# max2880base0.net
KiCad netlist of a schematic drawn in EAGLE
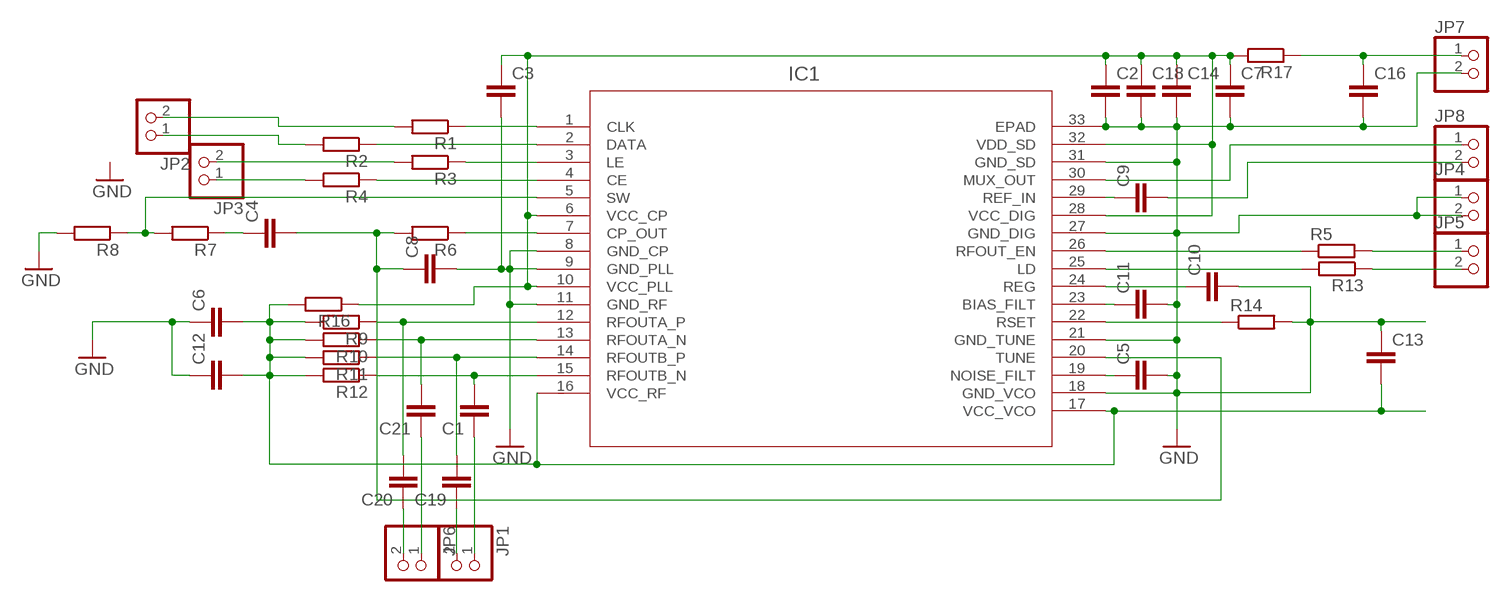
[diagram p0: schematic, sheet 1]

(export (version "E")
  (design (tool "Eeschema 10.0.6"))
  (components
    (comp (ref "C1")
      (value "C-EUC0805")
      (footprint "eagle-import:C0805")
      (libsource (lib "eagle-import") (part "C-EUC0805"))
    )
    (comp (ref "C2")
      (value "C-EUC0805")
      (footprint "eagle-import:C0805")
      (libsource (lib "eagle-import") (part "C-EUC0805"))
    )
    (comp (ref "C3")
      (value "C-EUC0805")
      (footprint "eagle-import:C0805")
      (libsource (lib "eagle-import") (part "C-EUC0805"))
    )
    (comp (ref "C4")
      (value "C-EUC0805")
      (footprint "eagle-import:C0805")
      (libsource (lib "eagle-import") (part "C-EUC0805"))
    )
    (comp (ref "C5")
      (value "C-EUC0805")
      (footprint "eagle-import:C0805")
      (libsource (lib "eagle-import") (part "C-EUC0805"))
    )
    (comp (ref "C6")
      (value "C-EUC0805")
      (footprint "eagle-import:C0805")
      (libsource (lib "eagle-import") (part "C-EUC0805"))
    )
    (comp (ref "C7")
      (value "C-EUC0805")
      (footprint "eagle-import:C0805")
      (libsource (lib "eagle-import") (part "C-EUC0805"))
    )
    (comp (ref "C8")
      (value "C-EUC0805")
      (footprint "eagle-import:C0805")
      (libsource (lib "eagle-import") (part "C-EUC0805"))
    )
    (comp (ref "C9")
      (value "C-EUC0805")
      (footprint "eagle-import:C0805")
      (libsource (lib "eagle-import") (part "C-EUC0805"))
    )
    (comp (ref "C10")
      (value "C-EUC0805")
      (footprint "eagle-import:C0805")
      (libsource (lib "eagle-import") (part "C-EUC0805"))
    )
    (comp (ref "C11")
      (value "C-EUC0805")
      (footprint "eagle-import:C0805")
      (libsource (lib "eagle-import") (part "C-EUC0805"))
    )
    (comp (ref "C12")
      (value "C-EUC0805")
      (footprint "eagle-import:C0805")
      (libsource (lib "eagle-import") (part "C-EUC0805"))
    )
    (comp (ref "C13")
      (value "C-EUC1206")
      (footprint "eagle-import:C1206")
      (libsource (lib "eagle-import") (part "C-EUC1206"))
    )
    (comp (ref "C14")
      (value "C-EUC1206")
      (footprint "eagle-import:C1206")
      (libsource (lib "eagle-import") (part "C-EUC1206"))
    )
    (comp (ref "C16")
      (value "C-EUC1206")
      (footprint "eagle-import:C1206")
      (libsource (lib "eagle-import") (part "C-EUC1206"))
    )
    (comp (ref "C18")
      (value "C-EUC1808")
      (footprint "eagle-import:C1808")
      (libsource (lib "eagle-import") (part "C-EUC1808"))
    )
    (comp (ref "C19")
      (value "C-EUC0805")
      (footprint "eagle-import:C0805")
      (libsource (lib "eagle-import") (part "C-EUC0805"))
    )
    (comp (ref "C20")
      (value "C-EUC0805")
      (footprint "eagle-import:C0805")
      (libsource (lib "eagle-import") (part "C-EUC0805"))
    )
    (comp (ref "C21")
      (value "C-EUC0805")
      (footprint "eagle-import:C0805")
      (libsource (lib "eagle-import") (part "C-EUC0805"))
    )
    (comp (ref "IC1")
      (value "MAX2870ETJ+")
      (footprint "eagle-import:21-0140L_T3255-5")
      (fields (field (name "MANUFACTURER_PART_NUMBER") "max2870etj+"))
      (libsource (lib "eagle-import") (part "MAX2870ETJ+"))
    )
    (comp (ref "JP1")
      (value "PINHD-1X2")
      (footprint "eagle-import:1X02")
      (libsource (lib "eagle-import") (part "PINHD-1X2"))
    )
    (comp (ref "JP2")
      (value "PINHD-1X2")
      (footprint "eagle-import:1X02")
      (libsource (lib "eagle-import") (part "PINHD-1X2"))
    )
    (comp (ref "JP3")
      (value "PINHD-1X2")
      (footprint "eagle-import:1X02")
      (libsource (lib "eagle-import") (part "PINHD-1X2"))
    )
    (comp (ref "JP4")
      (value "PINHD-1X2")
      (footprint "eagle-import:1X02")
      (libsource (lib "eagle-import") (part "PINHD-1X2"))
    )
    (comp (ref "JP5")
      (value "PINHD-1X2")
      (footprint "eagle-import:1X02")
      (libsource (lib "eagle-import") (part "PINHD-1X2"))
    )
    (comp (ref "JP6")
      (value "PINHD-1X2")
      (footprint "eagle-import:1X02")
      (libsource (lib "eagle-import") (part "PINHD-1X2"))
    )
    (comp (ref "JP7")
      (value "PINHD-1X2")
      (footprint "eagle-import:1X02")
      (libsource (lib "eagle-import") (part "PINHD-1X2"))
    )
    (comp (ref "JP8")
      (value "PINHD-1X2")
      (footprint "eagle-import:1X02")
      (libsource (lib "eagle-import") (part "PINHD-1X2"))
    )
    (comp (ref "R1")
      (value "R-EU_R0805")
      (footprint "eagle-import:R0805")
      (libsource (lib "eagle-import") (part "R-EU_R0805"))
    )
    (comp (ref "R2")
      (value "R-EU_R0805")
      (footprint "eagle-import:R0805")
      (libsource (lib "eagle-import") (part "R-EU_R0805"))
    )
    (comp (ref "R3")
      (value "R-EU_R0805")
      (footprint "eagle-import:R0805")
      (libsource (lib "eagle-import") (part "R-EU_R0805"))
    )
    (comp (ref "R4")
      (value "R-EU_R0805")
      (footprint "eagle-import:R0805")
      (libsource (lib "eagle-import") (part "R-EU_R0805"))
    )
    (comp (ref "R5")
      (value "R-EU_R0805")
      (footprint "eagle-import:R0805")
      (libsource (lib "eagle-import") (part "R-EU_R0805"))
    )
    (comp (ref "R6")
      (value "R-EU_R0805")
      (footprint "eagle-import:R0805")
      (libsource (lib "eagle-import") (part "R-EU_R0805"))
    )
    (comp (ref "R7")
      (value "R-EU_R0805")
      (footprint "eagle-import:R0805")
      (libsource (lib "eagle-import") (part "R-EU_R0805"))
    )
    (comp (ref "R8")
      (value "R-EU_R0805")
      (footprint "eagle-import:R0805")
      (libsource (lib "eagle-import") (part "R-EU_R0805"))
    )
    (comp (ref "R9")
      (value "R-EU_M0805")
      (footprint "eagle-import:M0805")
      (libsource (lib "eagle-import") (part "R-EU_M0805"))
    )
    (comp (ref "R10")
      (value "R-EU_M0805")
      (footprint "eagle-import:M0805")
      (libsource (lib "eagle-import") (part "R-EU_M0805"))
    )
    (comp (ref "R11")
      (value "R-EU_M0805")
      (footprint "eagle-import:M0805")
      (libsource (lib "eagle-import") (part "R-EU_M0805"))
    )
    (comp (ref "R12")
      (value "R-EU_M0805")
      (footprint "eagle-import:M0805")
      (libsource (lib "eagle-import") (part "R-EU_M0805"))
    )
    (comp (ref "R13")
      (value "R-EU_R0805")
      (footprint "eagle-import:R0805")
      (libsource (lib "eagle-import") (part "R-EU_R0805"))
    )
    (comp (ref "R14")
      (value "R-EU_R0805")
      (footprint "eagle-import:R0805")
      (libsource (lib "eagle-import") (part "R-EU_R0805"))
    )
    (comp (ref "R16")
      (value "R-EU_R1206")
      (footprint "eagle-import:R1206")
      (libsource (lib "eagle-import") (part "R-EU_R1206"))
    )
    (comp (ref "R17")
      (value "R-EU_R0805")
      (footprint "eagle-import:R0805")
      (libsource (lib "eagle-import") (part "R-EU_R0805"))
    )
  )
  (nets
    (net (code "1") (name "GND") (class "Default")
      (node (ref "C10") (pin "2") (pinfunction "2_2") (pintype "passive"))
      (node (ref "C11") (pin "2") (pinfunction "2_2") (pintype "passive"))
      (node (ref "C12") (pin "1") (pinfunction "1_1") (pintype "passive"))
      (node (ref "C13") (pin "1") (pinfunction "1_1") (pintype "passive"))
      (node (ref "C14") (pin "2") (pinfunction "2_2") (pintype "passive"))
      (node (ref "C16") (pin "2") (pinfunction "2_2") (pintype "passive"))
      (node (ref "C18") (pin "2") (pinfunction "2_2") (pintype "passive"))
      (node (ref "C2") (pin "2") (pinfunction "2_2") (pintype "passive"))
      (node (ref "C3") (pin "2") (pinfunction "2_2") (pintype "passive"))
      (node (ref "C5") (pin "2") (pinfunction "2_2") (pintype "passive"))
      (node (ref "C6") (pin "1") (pinfunction "1_1") (pintype "passive"))
      (node (ref "C7") (pin "2") (pinfunction "2_2") (pintype "passive"))
      (node (ref "C8") (pin "2") (pinfunction "2_2") (pintype "passive"))
      (node (ref "IC1") (pin "11") (pinfunction "GND_RF_11") (pintype "power_in"))
      (node (ref "IC1") (pin "18") (pinfunction "GND_VCO_18") (pintype "power_in"))
      (node (ref "IC1") (pin "21") (pinfunction "GND_TUNE_21") (pintype "power_in"))
      (node (ref "IC1") (pin "27") (pinfunction "GND_DIG_27") (pintype "power_in"))
      (node (ref "IC1") (pin "31") (pinfunction "GND_SD_31") (pintype "power_in"))
      (node (ref "IC1") (pin "33") (pinfunction "EPAD_33") (pintype "passive"))
      (node (ref "IC1") (pin "8") (pinfunction "GND_CP_8") (pintype "power_in"))
      (node (ref "IC1") (pin "9") (pinfunction "GND_PLL_9") (pintype "power_in"))
      (node (ref "JP4") (pin "1") (pinfunction "1_1") (pintype "passive"))
      (node (ref "JP4") (pin "2") (pinfunction "2_2") (pintype "passive"))
      (node (ref "JP7") (pin "2") (pinfunction "2_2") (pintype "passive"))
      (node (ref "R14") (pin "2") (pinfunction "2_2") (pintype "passive"))
      (node (ref "R8") (pin "2") (pinfunction "2_2") (pintype "passive"))
    )
    (net (code "2") (name "Net-(C1-Pad1)") (class "Default")
      (node (ref "C1") (pin "1") (pinfunction "1_1") (pintype "passive"))
      (node (ref "JP1") (pin "1") (pinfunction "1_1") (pintype "passive"))
    )
    (net (code "3") (name "Net-(C4-Pad1)") (class "Default")
      (node (ref "C4") (pin "1") (pinfunction "1_1") (pintype "passive"))
      (node (ref "R7") (pin "1") (pinfunction "1_1") (pintype "passive"))
    )
    (net (code "4") (name "Net-(C9-Pad2)") (class "Default")
      (node (ref "C9") (pin "2") (pinfunction "2_2") (pintype "passive"))
      (node (ref "JP8") (pin "2") (pinfunction "2_2") (pintype "passive"))
    )
    (net (code "5") (name "Net-(C16-Pad1)") (class "Default")
      (node (ref "C16") (pin "1") (pinfunction "1_1") (pintype "passive"))
      (node (ref "JP7") (pin "1") (pinfunction "1_1") (pintype "passive"))
      (node (ref "R17") (pin "1") (pinfunction "1_1") (pintype "passive"))
    )
    (net (code "6") (name "Net-(C19-Pad1)") (class "Default")
      (node (ref "C19") (pin "1") (pinfunction "1_1") (pintype "passive"))
      (node (ref "JP1") (pin "2") (pinfunction "2_2") (pintype "passive"))
    )
    (net (code "7") (name "Net-(C20-Pad1)") (class "Default")
      (node (ref "C20") (pin "1") (pinfunction "1_1") (pintype "passive"))
      (node (ref "JP6") (pin "2") (pinfunction "2_2") (pintype "passive"))
    )
    (net (code "8") (name "Net-(C21-Pad1)") (class "Default")
      (node (ref "C21") (pin "1") (pinfunction "1_1") (pintype "passive"))
      (node (ref "JP6") (pin "1") (pinfunction "1_1") (pintype "passive"))
    )
    (net (code "9") (name "Net-(IC1-BIAS_FILT)") (class "Default")
      (node (ref "C11") (pin "1") (pinfunction "1_1") (pintype "passive"))
      (node (ref "IC1") (pin "23") (pinfunction "BIAS_FILT_23") (pintype "passive"))
    )
    (net (code "10") (name "Net-(IC1-CE)") (class "Default")
      (node (ref "IC1") (pin "4") (pinfunction "CE_4") (pintype "passive"))
      (node (ref "R4") (pin "1") (pinfunction "1_1") (pintype "passive"))
    )
    (net (code "11") (name "Net-(IC1-CLK)") (class "Default")
      (node (ref "IC1") (pin "1") (pinfunction "CLK_1") (pintype "passive"))
      (node (ref "R1") (pin "1") (pinfunction "1_1") (pintype "passive"))
    )
    (net (code "12") (name "Net-(IC1-CP_OUT)") (class "Default")
      (node (ref "IC1") (pin "7") (pinfunction "CP_OUT_7") (pintype "output"))
      (node (ref "R6") (pin "1") (pinfunction "1_1") (pintype "passive"))
    )
    (net (code "13") (name "Net-(IC1-DATA)") (class "Default")
      (node (ref "IC1") (pin "2") (pinfunction "DATA_2") (pintype "passive"))
      (node (ref "R2") (pin "1") (pinfunction "1_1") (pintype "passive"))
    )
    (net (code "14") (name "Net-(IC1-LD)") (class "Default")
      (node (ref "IC1") (pin "25") (pinfunction "LD_25") (pintype "passive"))
      (node (ref "R13") (pin "2") (pinfunction "2_2") (pintype "passive"))
    )
    (net (code "15") (name "Net-(IC1-LE)") (class "Default")
      (node (ref "IC1") (pin "3") (pinfunction "LE_3") (pintype "passive"))
      (node (ref "R3") (pin "1") (pinfunction "1_1") (pintype "passive"))
    )
    (net (code "16") (name "Net-(IC1-MUX_OUT)") (class "Default")
      (node (ref "IC1") (pin "30") (pinfunction "MUX_OUT_30") (pintype "output"))
      (node (ref "JP8") (pin "1") (pinfunction "1_1") (pintype "passive"))
    )
    (net (code "17") (name "Net-(IC1-NOISE_FILT)") (class "Default")
      (node (ref "C5") (pin "1") (pinfunction "1_1") (pintype "passive"))
      (node (ref "IC1") (pin "19") (pinfunction "NOISE_FILT_19") (pintype "passive"))
    )
    (net (code "18") (name "Net-(IC1-REF_IN)") (class "Default")
      (node (ref "C9") (pin "1") (pinfunction "1_1") (pintype "passive"))
      (node (ref "IC1") (pin "29") (pinfunction "REF_IN_29") (pintype "input"))
    )
    (net (code "19") (name "Net-(IC1-REG)") (class "Default")
      (node (ref "C10") (pin "1") (pinfunction "1_1") (pintype "passive"))
      (node (ref "IC1") (pin "24") (pinfunction "REG_24") (pintype "passive"))
    )
    (net (code "20") (name "Net-(IC1-RFOUTA_N)") (class "Default")
      (node (ref "C21") (pin "2") (pinfunction "2_2") (pintype "passive"))
      (node (ref "IC1") (pin "13") (pinfunction "RFOUTA_N_13") (pintype "output"))
      (node (ref "R10") (pin "1") (pinfunction "1_1") (pintype "passive"))
    )
    (net (code "21") (name "Net-(IC1-RFOUTA_P)") (class "Default")
      (node (ref "C20") (pin "2") (pinfunction "2_2") (pintype "passive"))
      (node (ref "IC1") (pin "12") (pinfunction "RFOUTA_P_12") (pintype "output"))
      (node (ref "R9") (pin "1") (pinfunction "1_1") (pintype "passive"))
    )
    (net (code "22") (name "Net-(IC1-RFOUTB_N)") (class "Default")
      (node (ref "C1") (pin "2") (pinfunction "2_2") (pintype "passive"))
      (node (ref "IC1") (pin "15") (pinfunction "RFOUTB_N_15") (pintype "output"))
      (node (ref "R12") (pin "1") (pinfunction "1_1") (pintype "passive"))
    )
    (net (code "23") (name "Net-(IC1-RFOUTB_P)") (class "Default")
      (node (ref "C19") (pin "2") (pinfunction "2_2") (pintype "passive"))
      (node (ref "IC1") (pin "14") (pinfunction "RFOUTB_P_14") (pintype "output"))
      (node (ref "R11") (pin "1") (pinfunction "1_1") (pintype "passive"))
    )
    (net (code "24") (name "Net-(IC1-RFOUT_EN)") (class "Default")
      (node (ref "IC1") (pin "26") (pinfunction "RFOUT_EN_26") (pintype "output"))
      (node (ref "R5") (pin "1") (pinfunction "1_1") (pintype "passive"))
    )
    (net (code "25") (name "Net-(IC1-RSET)") (class "Default")
      (node (ref "IC1") (pin "22") (pinfunction "RSET_22") (pintype "passive"))
      (node (ref "R14") (pin "1") (pinfunction "1_1") (pintype "passive"))
    )
    (net (code "26") (name "Net-(IC1-SW)") (class "Default")
      (node (ref "IC1") (pin "5") (pinfunction "SW_5") (pintype "passive"))
      (node (ref "R7") (pin "2") (pinfunction "2_2") (pintype "passive"))
      (node (ref "R8") (pin "1") (pinfunction "1_1") (pintype "passive"))
    )
    (net (code "27") (name "Net-(IC1-TUNE)") (class "Default")
      (node (ref "C4") (pin "2") (pinfunction "2_2") (pintype "passive"))
      (node (ref "C8") (pin "1") (pinfunction "1_1") (pintype "passive"))
      (node (ref "IC1") (pin "20") (pinfunction "TUNE_20") (pintype "passive"))
      (node (ref "R6") (pin "2") (pinfunction "2_2") (pintype "passive"))
    )
    (net (code "28") (name "Net-(IC1-VCC_CP)") (class "Default")
      (node (ref "C14") (pin "1") (pinfunction "1_1") (pintype "passive"))
      (node (ref "C18") (pin "1") (pinfunction "1_1") (pintype "passive"))
      (node (ref "C2") (pin "1") (pinfunction "1_1") (pintype "passive"))
      (node (ref "C3") (pin "1") (pinfunction "1_1") (pintype "passive"))
      (node (ref "C7") (pin "1") (pinfunction "1_1") (pintype "passive"))
      (node (ref "IC1") (pin "10") (pinfunction "VCC_PLL_10") (pintype "power_in"))
      (node (ref "IC1") (pin "28") (pinfunction "VCC_DIG_28") (pintype "power_in"))
      (node (ref "IC1") (pin "32") (pinfunction "VDD_SD_32") (pintype "power_in"))
      (node (ref "IC1") (pin "6") (pinfunction "VCC_CP_6") (pintype "power_in"))
      (node (ref "R16") (pin "1") (pinfunction "1_1") (pintype "passive"))
      (node (ref "R17") (pin "2") (pinfunction "2_2") (pintype "passive"))
    )
    (net (code "29") (name "Net-(IC1-VCC_RF)") (class "Default")
      (node (ref "C12") (pin "2") (pinfunction "2_2") (pintype "passive"))
      (node (ref "C13") (pin "2") (pinfunction "2_2") (pintype "passive"))
      (node (ref "C6") (pin "2") (pinfunction "2_2") (pintype "passive"))
      (node (ref "IC1") (pin "16") (pinfunction "VCC_RF_16") (pintype "power_in"))
      (node (ref "IC1") (pin "17") (pinfunction "VCC_VCO_17") (pintype "power_in"))
      (node (ref "R10") (pin "2") (pinfunction "2_2") (pintype "passive"))
      (node (ref "R11") (pin "2") (pinfunction "2_2") (pintype "passive"))
      (node (ref "R12") (pin "2") (pinfunction "2_2") (pintype "passive"))
      (node (ref "R16") (pin "2") (pinfunction "2_2") (pintype "passive"))
      (node (ref "R9") (pin "2") (pinfunction "2_2") (pintype "passive"))
    )
    (net (code "30") (name "Net-(JP2-Pad1)") (class "Default")
      (node (ref "JP2") (pin "1") (pinfunction "1_1") (pintype "passive"))
      (node (ref "R2") (pin "2") (pinfunction "2_2") (pintype "passive"))
    )
    (net (code "31") (name "Net-(JP2-Pad2)") (class "Default")
      (node (ref "JP2") (pin "2") (pinfunction "2_2") (pintype "passive"))
      (node (ref "R1") (pin "2") (pinfunction "2_2") (pintype "passive"))
    )
    (net (code "32") (name "Net-(JP3-Pad1)") (class "Default")
      (node (ref "JP3") (pin "1") (pinfunction "1_1") (pintype "passive"))
      (node (ref "R4") (pin "2") (pinfunction "2_2") (pintype "passive"))
    )
    (net (code "33") (name "Net-(JP3-Pad2)") (class "Default")
      (node (ref "JP3") (pin "2") (pinfunction "2_2") (pintype "passive"))
      (node (ref "R3") (pin "2") (pinfunction "2_2") (pintype "passive"))
    )
    (net (code "34") (name "Net-(JP5-Pad1)") (class "Default")
      (node (ref "JP5") (pin "1") (pinfunction "1_1") (pintype "passive"))
      (node (ref "R5") (pin "2") (pinfunction "2_2") (pintype "passive"))
    )
    (net (code "35") (name "Net-(JP5-Pad2)") (class "Default")
      (node (ref "JP5") (pin "2") (pinfunction "2_2") (pintype "passive"))
      (node (ref "R13") (pin "1") (pinfunction "1_1") (pintype "passive"))
    )
  )
)
